# design_EasyDEA.net
KiCad netlist of a schematic drawn in EasyEDA
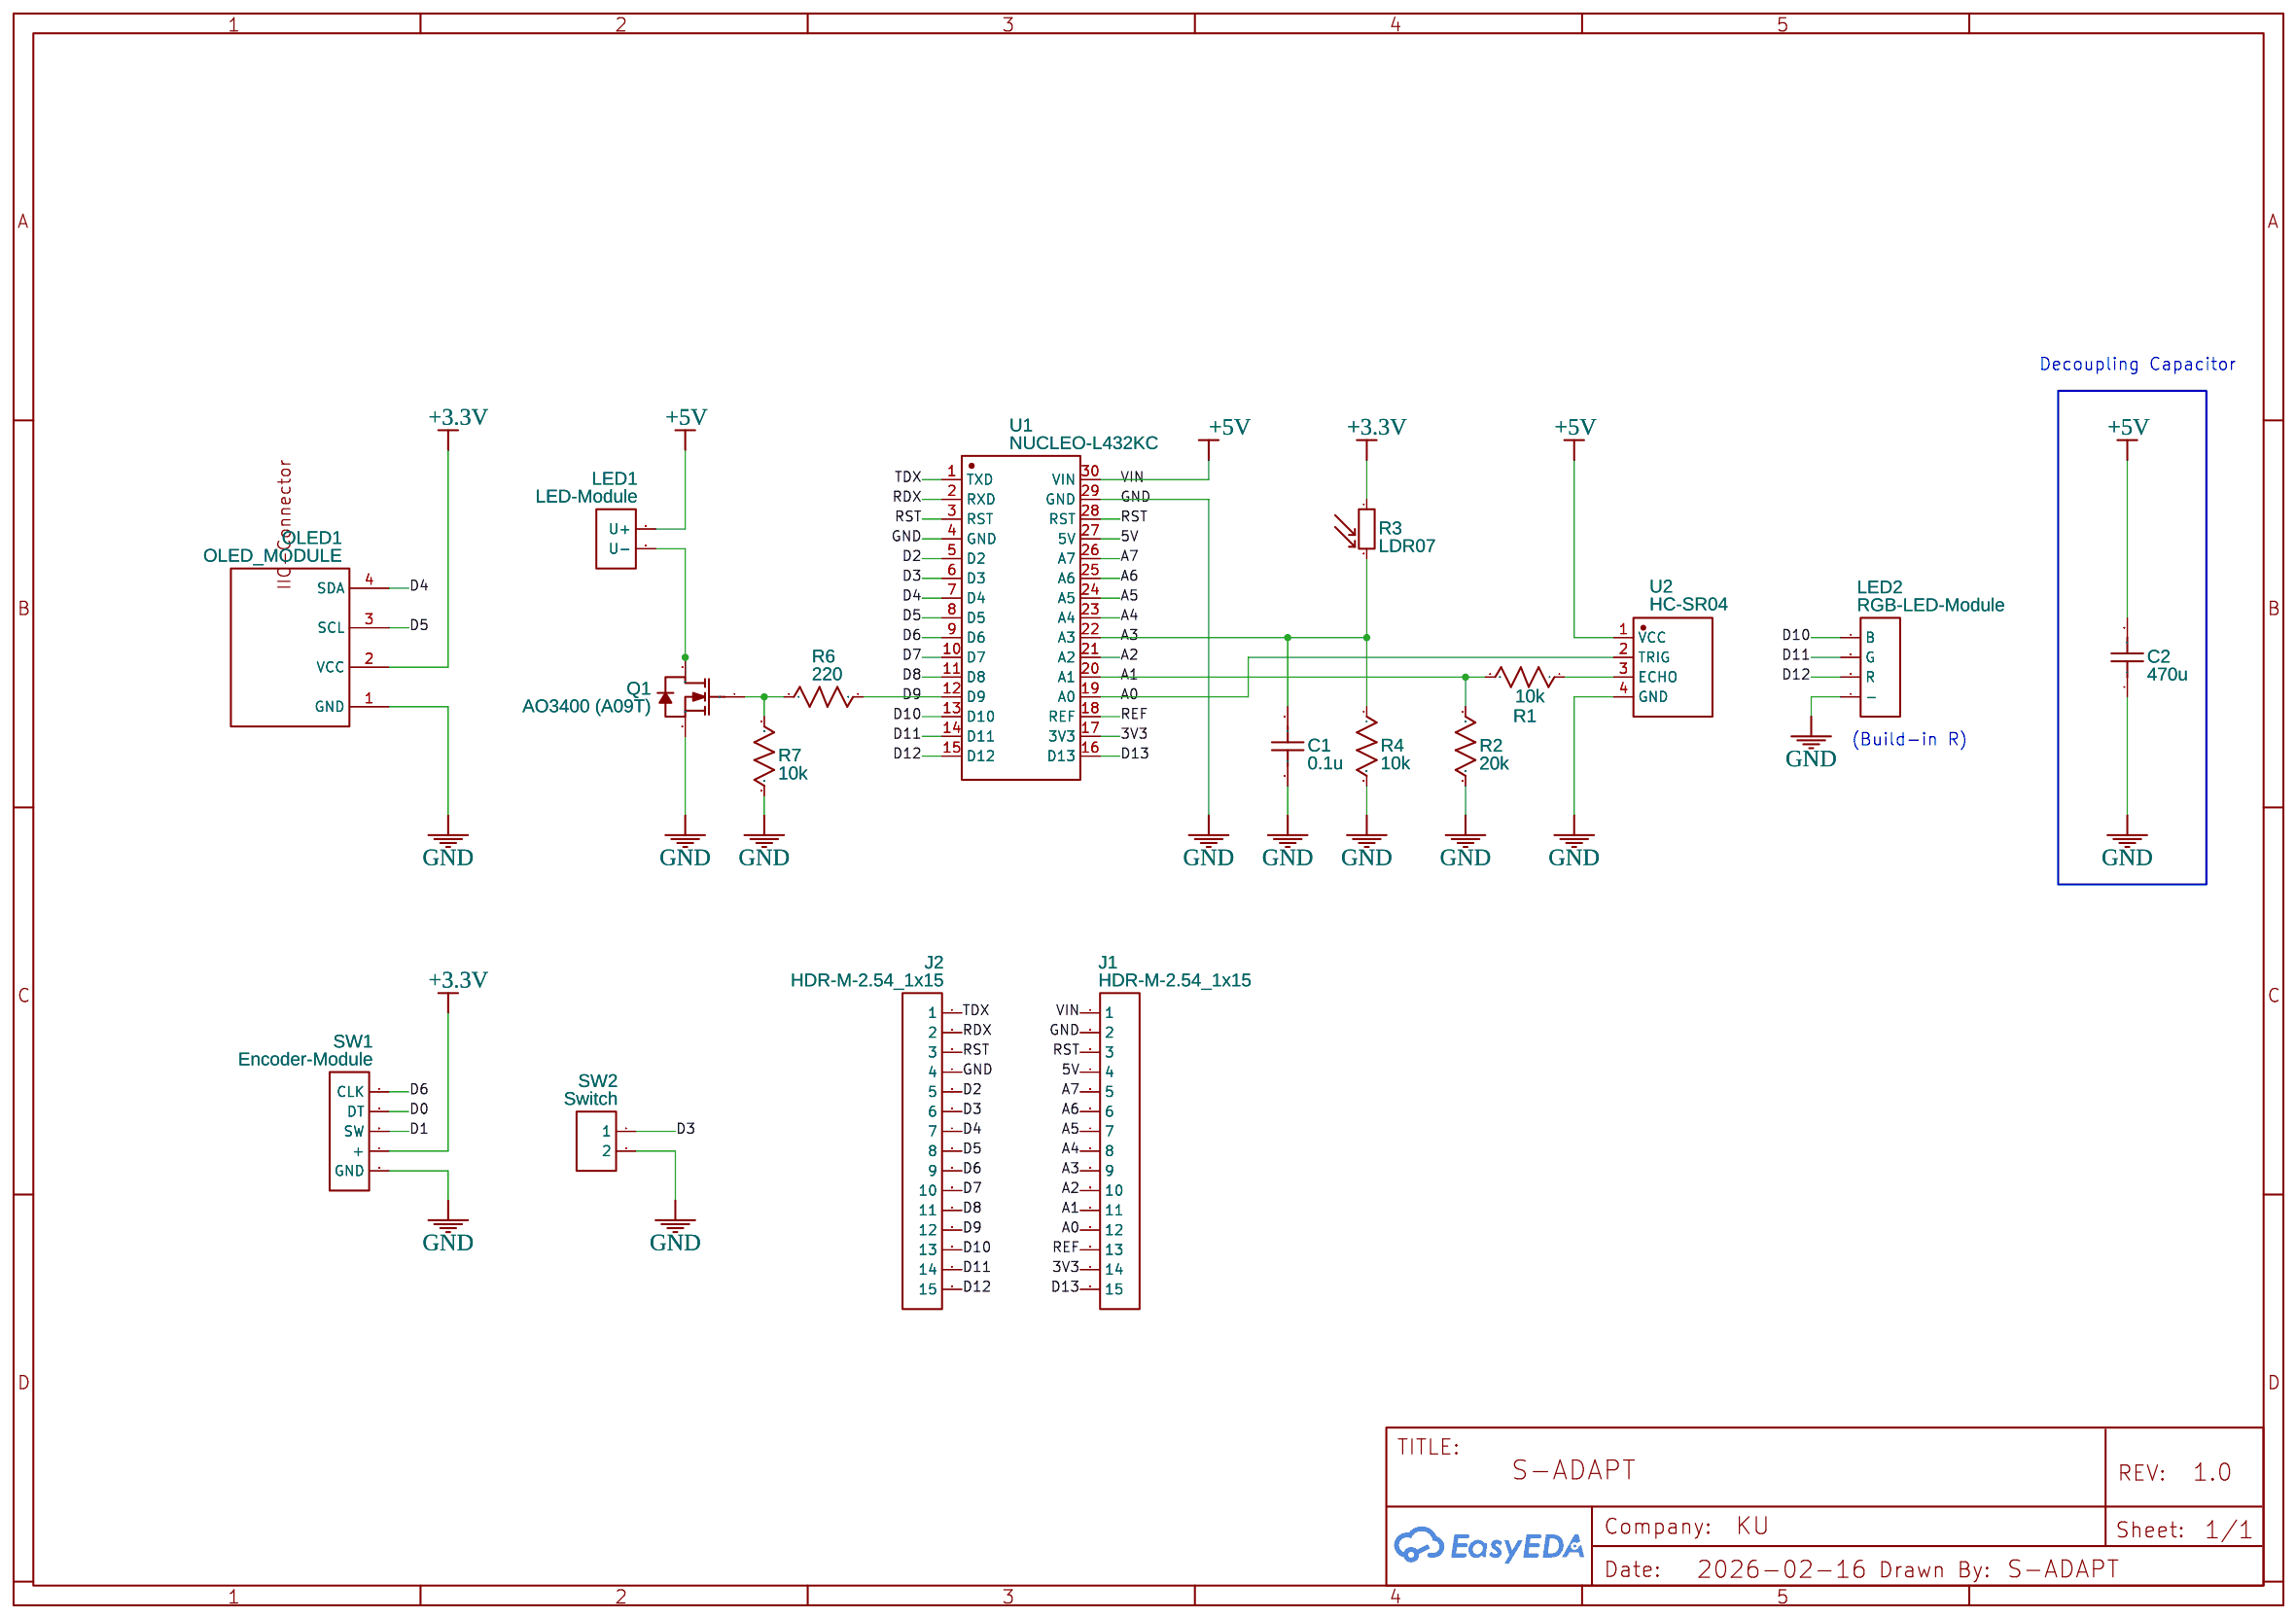
[diagram p0: schematic sheet]

(export (version "E")
  (design (tool "Eeschema 10.0.6"))
  (components
    (comp (ref "C1") (value "0.1u") (libsource (lib "") (part "C_0603_US")))
    (comp (ref "C2") (value "470u") (libsource (lib "") (part "C_0603_US")))
    (comp (ref "J1") (value "HDR-M-2.54_1x15") (libsource (lib "") (part "HDR-M-2.54_1x15")))
    (comp (ref "J2") (value "HDR-M-2.54_1x15") (libsource (lib "") (part "HDR-M-2.54_1x15_1")))
    (comp (ref "LED1") (value "LED-Module") (libsource (lib "") (part "HDR-M-2.54_1x2_1")))
    (comp (ref "LED2") (value "RGB-LED-Module") (libsource (lib "") (part "HDR-F-2.54_1x4")))
    (comp (ref "OLED1")
      (value "OLED_MODULE")
      (fields (field (name "Manufacturer Part") "0.96OLED_4P_MODULE_JX"))
      (libsource (lib "") (part "0.96OLED_4P_MODULE_JX"))
    )
    (comp (ref "Q1")
      (value "AO3400 (A09T)")
      (fields (field (name "Manufacturer Part") "AO3400NSA") (field (name "Manufacturer") "DOWO(东沃)"))
      (libsource (lib "") (part "AO3400NSA"))
    )
    (comp (ref "R1") (value "10k") (libsource (lib "") (part "R_0603_US_1")))
    (comp (ref "R2") (value "20k") (libsource (lib "") (part "R_0603_US")))
    (comp (ref "R3") (value "LDR07") (libsource (lib "") (part "LDR07")))
    (comp (ref "R4") (value "10k") (libsource (lib "") (part "R_0603_US_2")))
    (comp (ref "R6") (value "220") (libsource (lib "") (part "R_0805_US_1")))
    (comp (ref "R7") (value "10k") (libsource (lib "") (part "R_0805_US")))
    (comp (ref "SW1") (value "Encoder-Module") (libsource (lib "") (part "HDR-F-2.54_1x5")))
    (comp (ref "SW2") (value "Switch") (libsource (lib "") (part "HDR-M-2.54_1x2")))
    (comp (ref "U1")
      (value "NUCLEO-L432KC")
      (fields (field (name "Manufacturer") "ST(意法半导体)"))
      (libsource (lib "") (part "NUCLEO-L432KC"))
    )
    (comp (ref "U2")
      (value "HC-SR04")
      (fields (field (name "Manufacturer") "Universal Microelectronics"))
      (libsource (lib "") (part "HC-SR04"))
    )
  )
  (nets
    (net (code "1") (name "+3.3V") (class "Default")
      (node (ref "OLED1") (pin "2") (pinfunction "VCC_2") (pintype "unspecified"))
      (node (ref "R3") (pin "1") (pintype "unspecified"))
      (node (ref "SW1") (pin "4") (pinfunction "+_4") (pintype "unspecified"))
    )
    (net (code "2") (name "+5V") (class "Default")
      (node (ref "C2") (pin "2") (pinfunction "2_2") (pintype "unspecified"))
      (node (ref "J1") (pin "1") (pinfunction "1_1") (pintype "unspecified"))
      (node (ref "LED1") (pin "1") (pinfunction "U+_1") (pintype "unspecified"))
      (node (ref "U1") (pin "30") (pinfunction "VIN_30") (pintype "unspecified"))
      (node (ref "U2") (pin "1") (pinfunction "VCC_1") (pintype "unspecified"))
    )
    (net (code "3") (name "/3V3") (class "Default")
      (node (ref "J1") (pin "14") (pinfunction "14_14") (pintype "unspecified"))
      (node (ref "U1") (pin "17") (pinfunction "3V3_17") (pintype "unspecified"))
    )
    (net (code "4") (name "/5V") (class "Default")
      (node (ref "J1") (pin "4") (pinfunction "4_4") (pintype "unspecified"))
      (node (ref "U1") (pin "27") (pinfunction "5V_27") (pintype "unspecified"))
    )
    (net (code "5") (name "/A0") (class "Default")
      (node (ref "J1") (pin "12") (pinfunction "12_12") (pintype "unspecified"))
      (node (ref "U1") (pin "19") (pinfunction "A0_19") (pintype "unspecified"))
      (node (ref "U2") (pin "2") (pinfunction "TRIG_2") (pintype "unspecified"))
    )
    (net (code "6") (name "/A1") (class "Default")
      (node (ref "J1") (pin "11") (pinfunction "11_11") (pintype "unspecified"))
      (node (ref "R1") (pin "2") (pinfunction "2_2") (pintype "unspecified"))
      (node (ref "R2") (pin "2") (pinfunction "2_2") (pintype "unspecified"))
      (node (ref "U1") (pin "20") (pinfunction "A1_20") (pintype "unspecified"))
    )
    (net (code "7") (name "/A2") (class "Default")
      (node (ref "J1") (pin "10") (pinfunction "10_10") (pintype "unspecified"))
      (node (ref "U1") (pin "21") (pinfunction "A2_21") (pintype "unspecified"))
    )
    (net (code "8") (name "/A3") (class "Default")
      (node (ref "C1") (pin "2") (pinfunction "2_2") (pintype "unspecified"))
      (node (ref "J1") (pin "9") (pinfunction "9_9") (pintype "unspecified"))
      (node (ref "R3") (pin "2") (pintype "unspecified"))
      (node (ref "R4") (pin "1") (pinfunction "1_1") (pintype "unspecified"))
      (node (ref "U1") (pin "22") (pinfunction "A3_22") (pintype "unspecified"))
    )
    (net (code "9") (name "/A4") (class "Default")
      (node (ref "J1") (pin "8") (pinfunction "8_8") (pintype "unspecified"))
      (node (ref "U1") (pin "23") (pinfunction "A4_23") (pintype "unspecified"))
    )
    (net (code "10") (name "/A5") (class "Default")
      (node (ref "J1") (pin "7") (pinfunction "7_7") (pintype "unspecified"))
      (node (ref "U1") (pin "24") (pinfunction "A5_24") (pintype "unspecified"))
    )
    (net (code "11") (name "/A6") (class "Default")
      (node (ref "J1") (pin "6") (pinfunction "6_6") (pintype "unspecified"))
      (node (ref "U1") (pin "25") (pinfunction "A6_25") (pintype "unspecified"))
    )
    (net (code "12") (name "/A7") (class "Default")
      (node (ref "J1") (pin "5") (pinfunction "5_5") (pintype "unspecified"))
      (node (ref "U1") (pin "26") (pinfunction "A7_26") (pintype "unspecified"))
    )
    (net (code "13") (name "/D0") (class "Default")
      (node (ref "SW1") (pin "2") (pinfunction "DT_2") (pintype "unspecified"))
    )
    (net (code "14") (name "/D1") (class "Default")
      (node (ref "SW1") (pin "3") (pinfunction "SW_3") (pintype "unspecified"))
    )
    (net (code "15") (name "/D2") (class "Default")
      (node (ref "J2") (pin "5") (pinfunction "5_5") (pintype "unspecified"))
      (node (ref "U1") (pin "5") (pinfunction "D2_5") (pintype "unspecified"))
    )
    (net (code "16") (name "/D3") (class "Default")
      (node (ref "J2") (pin "6") (pinfunction "6_6") (pintype "unspecified"))
      (node (ref "SW2") (pin "1") (pinfunction "1_1") (pintype "unspecified"))
      (node (ref "U1") (pin "6") (pinfunction "D3_6") (pintype "unspecified"))
    )
    (net (code "17") (name "/D4") (class "Default")
      (node (ref "J2") (pin "7") (pinfunction "7_7") (pintype "unspecified"))
      (node (ref "OLED1") (pin "4") (pinfunction "SDA_4") (pintype "unspecified"))
      (node (ref "U1") (pin "7") (pinfunction "D4_7") (pintype "unspecified"))
    )
    (net (code "18") (name "/D5") (class "Default")
      (node (ref "J2") (pin "8") (pinfunction "8_8") (pintype "unspecified"))
      (node (ref "OLED1") (pin "3") (pinfunction "SCL_3") (pintype "unspecified"))
      (node (ref "U1") (pin "8") (pinfunction "D5_8") (pintype "unspecified"))
    )
    (net (code "19") (name "/D6") (class "Default")
      (node (ref "J2") (pin "9") (pinfunction "9_9") (pintype "unspecified"))
      (node (ref "SW1") (pin "1") (pinfunction "CLK_1") (pintype "unspecified"))
      (node (ref "U1") (pin "9") (pinfunction "D6_9") (pintype "unspecified"))
    )
    (net (code "20") (name "/D7") (class "Default")
      (node (ref "J2") (pin "10") (pinfunction "10_10") (pintype "unspecified"))
      (node (ref "U1") (pin "10") (pinfunction "D7_10") (pintype "unspecified"))
    )
    (net (code "21") (name "/D8") (class "Default")
      (node (ref "J2") (pin "11") (pinfunction "11_11") (pintype "unspecified"))
      (node (ref "U1") (pin "11") (pinfunction "D8_11") (pintype "unspecified"))
    )
    (net (code "22") (name "/D9") (class "Default")
      (node (ref "J2") (pin "12") (pinfunction "12_12") (pintype "unspecified"))
      (node (ref "R6") (pin "2") (pinfunction "2_2") (pintype "unspecified"))
      (node (ref "U1") (pin "12") (pinfunction "D9_12") (pintype "unspecified"))
    )
    (net (code "23") (name "/D10") (class "Default")
      (node (ref "J2") (pin "13") (pinfunction "13_13") (pintype "unspecified"))
      (node (ref "LED2") (pin "1") (pinfunction "B_1") (pintype "unspecified"))
      (node (ref "U1") (pin "13") (pinfunction "D10_13") (pintype "unspecified"))
    )
    (net (code "24") (name "/D11") (class "Default")
      (node (ref "J2") (pin "14") (pinfunction "14_14") (pintype "unspecified"))
      (node (ref "LED2") (pin "2") (pinfunction "G_2") (pintype "unspecified"))
      (node (ref "U1") (pin "14") (pinfunction "D11_14") (pintype "unspecified"))
    )
    (net (code "25") (name "/D12") (class "Default")
      (node (ref "J2") (pin "15") (pinfunction "15_15") (pintype "unspecified"))
      (node (ref "LED2") (pin "3") (pinfunction "R_3") (pintype "unspecified"))
      (node (ref "U1") (pin "15") (pinfunction "D12_15") (pintype "unspecified"))
    )
    (net (code "26") (name "/D13") (class "Default")
      (node (ref "J1") (pin "15") (pinfunction "15_15") (pintype "unspecified"))
      (node (ref "U1") (pin "16") (pinfunction "D13_16") (pintype "unspecified"))
    )
    (net (code "27") (name "/RDX") (class "Default")
      (node (ref "J2") (pin "2") (pinfunction "2_2") (pintype "unspecified"))
      (node (ref "U1") (pin "2") (pinfunction "RXD_2") (pintype "unspecified"))
    )
    (net (code "28") (name "/REF") (class "Default")
      (node (ref "J1") (pin "13") (pinfunction "13_13") (pintype "unspecified"))
      (node (ref "U1") (pin "18") (pinfunction "REF_18") (pintype "unspecified"))
    )
    (net (code "29") (name "/RST") (class "Default")
      (node (ref "J1") (pin "3") (pinfunction "3_3") (pintype "unspecified"))
      (node (ref "J2") (pin "3") (pinfunction "3_3") (pintype "unspecified"))
      (node (ref "U1") (pin "28") (pinfunction "RST_28") (pintype "unspecified"))
      (node (ref "U1") (pin "3") (pinfunction "RST_3") (pintype "unspecified"))
    )
    (net (code "30") (name "/TDX") (class "Default")
      (node (ref "J2") (pin "1") (pinfunction "1_1") (pintype "unspecified"))
      (node (ref "U1") (pin "1") (pinfunction "TXD_1") (pintype "unspecified"))
    )
    (net (code "31") (name "GND") (class "Default")
      (node (ref "C1") (pin "1") (pinfunction "1_1") (pintype "unspecified"))
      (node (ref "C2") (pin "1") (pinfunction "1_1") (pintype "unspecified"))
      (node (ref "J1") (pin "2") (pinfunction "2_2") (pintype "unspecified"))
      (node (ref "J2") (pin "4") (pinfunction "4_4") (pintype "unspecified"))
      (node (ref "LED2") (pin "4") (pinfunction "-_4") (pintype "unspecified"))
      (node (ref "OLED1") (pin "1") (pinfunction "GND_1") (pintype "unspecified"))
      (node (ref "Q1") (pin "2") (pinfunction "S_2") (pintype "unspecified"))
      (node (ref "R2") (pin "1") (pinfunction "1_1") (pintype "unspecified"))
      (node (ref "R4") (pin "2") (pinfunction "2_2") (pintype "unspecified"))
      (node (ref "R7") (pin "1") (pinfunction "1_1") (pintype "unspecified"))
      (node (ref "SW1") (pin "5") (pinfunction "GND_5") (pintype "unspecified"))
      (node (ref "SW2") (pin "2") (pinfunction "2_2") (pintype "unspecified"))
      (node (ref "U1") (pin "29") (pinfunction "GND_29") (pintype "unspecified"))
      (node (ref "U1") (pin "4") (pinfunction "GND_4") (pintype "unspecified"))
      (node (ref "U2") (pin "4") (pinfunction "GND_4") (pintype "unspecified"))
    )
    (net (code "32") (name "Net-(LED1-U-)") (class "Default")
      (node (ref "LED1") (pin "2") (pinfunction "U-_2") (pintype "unspecified"))
      (node (ref "Q1") (pin "3") (pinfunction "D_3") (pintype "unspecified"))
    )
    (net (code "33") (name "Net-(Q1-G)") (class "Default")
      (node (ref "Q1") (pin "1") (pinfunction "G_1") (pintype "unspecified"))
      (node (ref "R6") (pin "1") (pinfunction "1_1") (pintype "unspecified"))
      (node (ref "R7") (pin "2") (pinfunction "2_2") (pintype "unspecified"))
    )
    (net (code "34") (name "Net-(U2-ECHO)") (class "Default")
      (node (ref "R1") (pin "1") (pinfunction "1_1") (pintype "unspecified"))
      (node (ref "U2") (pin "3") (pinfunction "ECHO_3") (pintype "unspecified"))
    )
  )
)
